# db_02.net
KiCad netlist of a schematic drawn in EAGLE
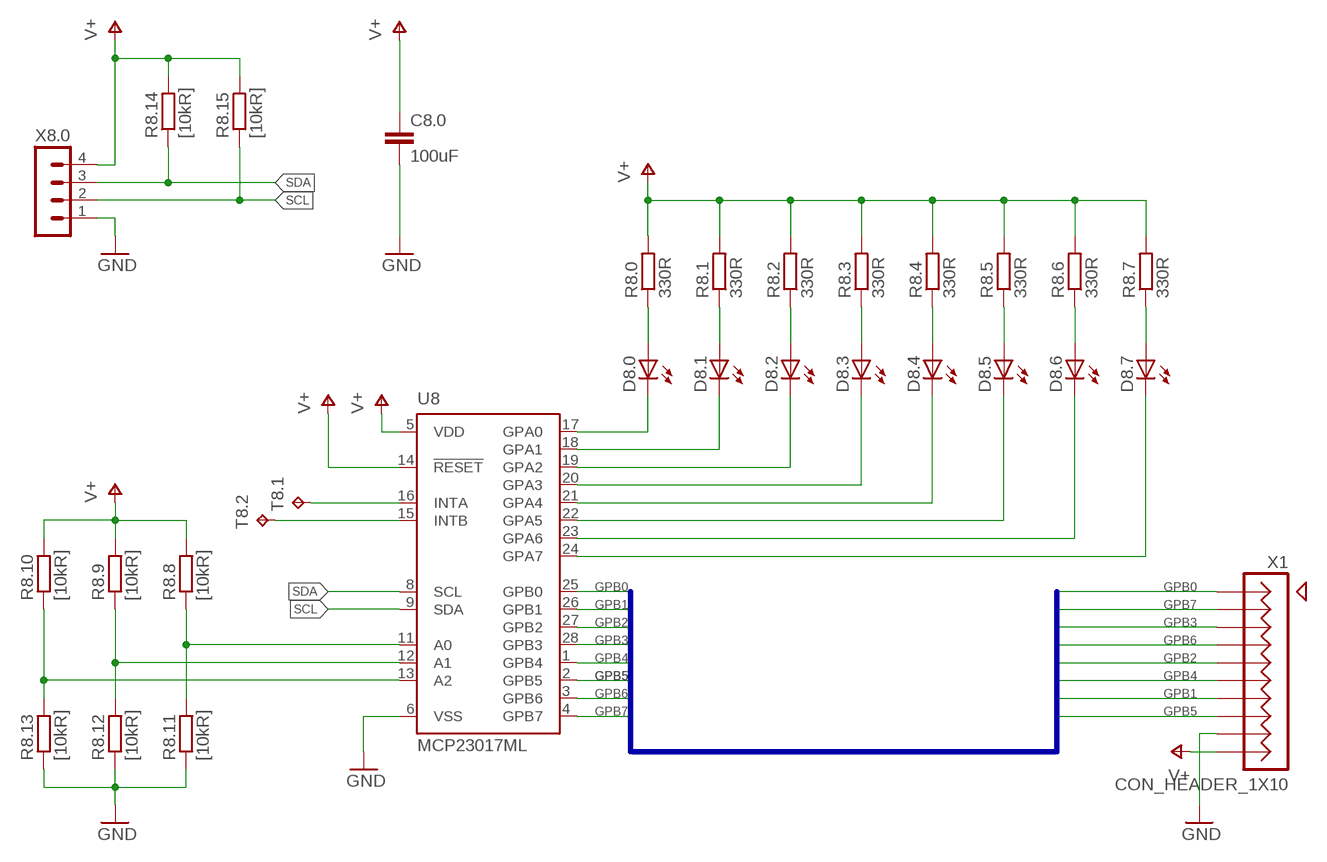
[diagram p0: schematic, sheet 1]

(export (version "E")
  (design (tool "Eeschema 10.0.6"))
  (components
    (comp (ref "C8.0")
      (value "100uF")
      (footprint "eagle-import:C0603")
      (libsource (lib "eagle-import") (part "C-EUC0603"))
    )
    (comp (ref "D8.0")
      (value "LEDCHIPLED_1206")
      (footprint "eagle-import:CHIPLED_1206")
      (libsource (lib "eagle-import") (part "LEDCHIPLED_1206"))
    )
    (comp (ref "D8.1")
      (value "LEDCHIPLED_1206")
      (footprint "eagle-import:CHIPLED_1206")
      (libsource (lib "eagle-import") (part "LEDCHIPLED_1206"))
    )
    (comp (ref "D8.2")
      (value "LEDCHIPLED_1206")
      (footprint "eagle-import:CHIPLED_1206")
      (libsource (lib "eagle-import") (part "LEDCHIPLED_1206"))
    )
    (comp (ref "D8.3")
      (value "LEDCHIPLED_1206")
      (footprint "eagle-import:CHIPLED_1206")
      (libsource (lib "eagle-import") (part "LEDCHIPLED_1206"))
    )
    (comp (ref "D8.4")
      (value "LEDCHIPLED_1206")
      (footprint "eagle-import:CHIPLED_1206")
      (libsource (lib "eagle-import") (part "LEDCHIPLED_1206"))
    )
    (comp (ref "D8.5")
      (value "LEDCHIPLED_1206")
      (footprint "eagle-import:CHIPLED_1206")
      (libsource (lib "eagle-import") (part "LEDCHIPLED_1206"))
    )
    (comp (ref "D8.6")
      (value "LEDCHIPLED_1206")
      (footprint "eagle-import:CHIPLED_1206")
      (libsource (lib "eagle-import") (part "LEDCHIPLED_1206"))
    )
    (comp (ref "D8.7")
      (value "LEDCHIPLED_1206")
      (footprint "eagle-import:CHIPLED_1206")
      (libsource (lib "eagle-import") (part "LEDCHIPLED_1206"))
    )
    (comp (ref "R8.0")
      (value "330R")
      (footprint "eagle-import:R0603")
      (libsource (lib "eagle-import") (part "R-EU_R0603"))
    )
    (comp (ref "R8.1")
      (value "330R")
      (footprint "eagle-import:R0603")
      (libsource (lib "eagle-import") (part "R-EU_R0603"))
    )
    (comp (ref "R8.2")
      (value "330R")
      (footprint "eagle-import:R0603")
      (libsource (lib "eagle-import") (part "R-EU_R0603"))
    )
    (comp (ref "R8.3")
      (value "330R")
      (footprint "eagle-import:R0603")
      (libsource (lib "eagle-import") (part "R-EU_R0603"))
    )
    (comp (ref "R8.4")
      (value "330R")
      (footprint "eagle-import:R0603")
      (libsource (lib "eagle-import") (part "R-EU_R0603"))
    )
    (comp (ref "R8.5")
      (value "330R")
      (footprint "eagle-import:R0603")
      (libsource (lib "eagle-import") (part "R-EU_R0603"))
    )
    (comp (ref "R8.6")
      (value "330R")
      (footprint "eagle-import:R0603")
      (libsource (lib "eagle-import") (part "R-EU_R0603"))
    )
    (comp (ref "R8.7")
      (value "330R")
      (footprint "eagle-import:R0603")
      (libsource (lib "eagle-import") (part "R-EU_R0603"))
    )
    (comp (ref "R8.8")
      (value "[10kR]")
      (footprint "eagle-import:R0402")
      (libsource (lib "eagle-import") (part "R-EU_R0402"))
    )
    (comp (ref "R8.9")
      (value "[10kR]")
      (footprint "eagle-import:R0402")
      (libsource (lib "eagle-import") (part "R-EU_R0402"))
    )
    (comp (ref "R8.10")
      (value "[10kR]")
      (footprint "eagle-import:R0402")
      (libsource (lib "eagle-import") (part "R-EU_R0402"))
    )
    (comp (ref "R8.11")
      (value "[10kR]")
      (footprint "eagle-import:R0402")
      (libsource (lib "eagle-import") (part "R-EU_R0402"))
    )
    (comp (ref "R8.12")
      (value "[10kR]")
      (footprint "eagle-import:R0402")
      (libsource (lib "eagle-import") (part "R-EU_R0402"))
    )
    (comp (ref "R8.13")
      (value "[10kR]")
      (footprint "eagle-import:R0402")
      (libsource (lib "eagle-import") (part "R-EU_R0402"))
    )
    (comp (ref "R8.14")
      (value "[10kR]")
      (footprint "eagle-import:R0402")
      (libsource (lib "eagle-import") (part "R-EU_R0402"))
    )
    (comp (ref "R8.15")
      (value "[10kR]")
      (footprint "eagle-import:R0402")
      (libsource (lib "eagle-import") (part "R-EU_R0402"))
    )
    (comp (ref "T8.1")
      (value "TPTP09SQ")
      (footprint "eagle-import:TP09SQ")
      (libsource (lib "eagle-import") (part "TPTP09SQ"))
    )
    (comp (ref "T8.2")
      (value "TPTP09SQ")
      (footprint "eagle-import:TP09SQ")
      (libsource (lib "eagle-import") (part "TPTP09SQ"))
    )
    (comp (ref "U8")
      (value "MCP23017ML")
      (footprint "eagle-import:QFN28-ML_6X6MM")
      (fields (field (name "MF") "MICROCHIP") (field (name "MPN") "MCP23017-E/ML"))
      (libsource (lib "eagle-import") (part "MCP23017ML"))
    )
    (comp (ref "X1")
      (value "CON_HEADER_1X10")
      (footprint "eagle-import:M1X10_SMD")
      (libsource (lib "eagle-import") (part "CON_HEADER_1X10"))
    )
    (comp (ref "X8.0")
      (value "MA04-1")
      (footprint "eagle-import:MA04-1")
      (libsource (lib "eagle-import") (part "MA04-1"))
    )
  )
  (nets
    (net (code "1") (name "/GPB0") (class "Default")
      (node (ref "U8") (pin "25") (pinfunction "GPB0_25") (pintype "bidirectional"))
      (node (ref "X1") (pin "P$1") (pinfunction "P$1_P$1") (pintype "bidirectional"))
    )
    (net (code "2") (name "/GPB1") (class "Default")
      (node (ref "U8") (pin "26") (pinfunction "GPB1_26") (pintype "bidirectional"))
      (node (ref "X1") (pin "P$7") (pinfunction "P$7_P$7") (pintype "bidirectional"))
    )
    (net (code "3") (name "/GPB2") (class "Default")
      (node (ref "U8") (pin "27") (pinfunction "GPB2_27") (pintype "bidirectional"))
      (node (ref "X1") (pin "P$5") (pinfunction "P$5_P$5") (pintype "bidirectional"))
    )
    (net (code "4") (name "/GPB3") (class "Default")
      (node (ref "U8") (pin "28") (pinfunction "GPB3_28") (pintype "bidirectional"))
      (node (ref "X1") (pin "P$3") (pinfunction "P$3_P$3") (pintype "bidirectional"))
    )
    (net (code "5") (name "/GPB4") (class "Default")
      (node (ref "U8") (pin "1") (pinfunction "GPB4_1") (pintype "bidirectional"))
      (node (ref "X1") (pin "P$6") (pinfunction "P$6_P$6") (pintype "bidirectional"))
    )
    (net (code "6") (name "/GPB5") (class "Default")
      (node (ref "U8") (pin "2") (pinfunction "GPB5_2") (pintype "bidirectional"))
      (node (ref "X1") (pin "P$8") (pinfunction "P$8_P$8") (pintype "bidirectional"))
    )
    (net (code "7") (name "/GPB6") (class "Default")
      (node (ref "U8") (pin "3") (pinfunction "GPB6_3") (pintype "bidirectional"))
      (node (ref "X1") (pin "P$4") (pinfunction "P$4_P$4") (pintype "bidirectional"))
    )
    (net (code "8") (name "/GPB7") (class "Default")
      (node (ref "U8") (pin "4") (pinfunction "GPB7_4") (pintype "bidirectional"))
      (node (ref "X1") (pin "P$2") (pinfunction "P$2_P$2") (pintype "bidirectional"))
    )
    (net (code "9") (name "GND") (class "Default")
      (node (ref "C8.0") (pin "2") (pinfunction "2_2") (pintype "passive"))
      (node (ref "R8.11") (pin "1") (pinfunction "1_1") (pintype "passive"))
      (node (ref "R8.12") (pin "1") (pinfunction "1_1") (pintype "passive"))
      (node (ref "R8.13") (pin "1") (pinfunction "1_1") (pintype "passive"))
      (node (ref "U8") (pin "6") (pinfunction "VSS_6") (pintype "power_in"))
      (node (ref "X1") (pin "P$9") (pinfunction "P$9_P$9") (pintype "bidirectional"))
      (node (ref "X8.0") (pin "1") (pinfunction "1_1") (pintype "passive"))
    )
    (net (code "10") (name "Net-(D8.0-PadA)") (class "Default")
      (node (ref "D8.0") (pin "A") (pinfunction "A_A") (pintype "passive"))
      (node (ref "R8.0") (pin "1") (pinfunction "1_1") (pintype "passive"))
    )
    (net (code "11") (name "Net-(D8.1-PadA)") (class "Default")
      (node (ref "D8.1") (pin "A") (pinfunction "A_A") (pintype "passive"))
      (node (ref "R8.1") (pin "1") (pinfunction "1_1") (pintype "passive"))
    )
    (net (code "12") (name "Net-(D8.2-PadA)") (class "Default")
      (node (ref "D8.2") (pin "A") (pinfunction "A_A") (pintype "passive"))
      (node (ref "R8.2") (pin "1") (pinfunction "1_1") (pintype "passive"))
    )
    (net (code "13") (name "Net-(D8.3-PadA)") (class "Default")
      (node (ref "D8.3") (pin "A") (pinfunction "A_A") (pintype "passive"))
      (node (ref "R8.3") (pin "1") (pinfunction "1_1") (pintype "passive"))
    )
    (net (code "14") (name "Net-(D8.4-PadA)") (class "Default")
      (node (ref "D8.4") (pin "A") (pinfunction "A_A") (pintype "passive"))
      (node (ref "R8.4") (pin "1") (pinfunction "1_1") (pintype "passive"))
    )
    (net (code "15") (name "Net-(D8.5-PadA)") (class "Default")
      (node (ref "D8.5") (pin "A") (pinfunction "A_A") (pintype "passive"))
      (node (ref "R8.5") (pin "1") (pinfunction "1_1") (pintype "passive"))
    )
    (net (code "16") (name "Net-(D8.6-PadA)") (class "Default")
      (node (ref "D8.6") (pin "A") (pinfunction "A_A") (pintype "passive"))
      (node (ref "R8.6") (pin "1") (pinfunction "1_1") (pintype "passive"))
    )
    (net (code "17") (name "Net-(D8.7-PadA)") (class "Default")
      (node (ref "D8.7") (pin "A") (pinfunction "A_A") (pintype "passive"))
      (node (ref "R8.7") (pin "1") (pinfunction "1_1") (pintype "passive"))
    )
    (net (code "18") (name "Net-(U8-A0)") (class "Default")
      (node (ref "R8.11") (pin "2") (pinfunction "2_2") (pintype "passive"))
      (node (ref "R8.8") (pin "1") (pinfunction "1_1") (pintype "passive"))
      (node (ref "U8") (pin "11") (pinfunction "A0_11") (pintype "input"))
    )
    (net (code "19") (name "Net-(U8-A1)") (class "Default")
      (node (ref "R8.12") (pin "2") (pinfunction "2_2") (pintype "passive"))
      (node (ref "R8.9") (pin "1") (pinfunction "1_1") (pintype "passive"))
      (node (ref "U8") (pin "12") (pinfunction "A1_12") (pintype "input"))
    )
    (net (code "20") (name "Net-(U8-A2)") (class "Default")
      (node (ref "R8.10") (pin "1") (pinfunction "1_1") (pintype "passive"))
      (node (ref "R8.13") (pin "2") (pinfunction "2_2") (pintype "passive"))
      (node (ref "U8") (pin "13") (pinfunction "A2_13") (pintype "input"))
    )
    (net (code "21") (name "Net-(U8-GPA0)") (class "Default")
      (node (ref "D8.0") (pin "C") (pinfunction "C_C") (pintype "passive"))
      (node (ref "U8") (pin "17") (pinfunction "GPA0_17") (pintype "bidirectional"))
    )
    (net (code "22") (name "Net-(U8-GPA1)") (class "Default")
      (node (ref "D8.1") (pin "C") (pinfunction "C_C") (pintype "passive"))
      (node (ref "U8") (pin "18") (pinfunction "GPA1_18") (pintype "bidirectional"))
    )
    (net (code "23") (name "Net-(U8-GPA2)") (class "Default")
      (node (ref "D8.2") (pin "C") (pinfunction "C_C") (pintype "passive"))
      (node (ref "U8") (pin "19") (pinfunction "GPA2_19") (pintype "bidirectional"))
    )
    (net (code "24") (name "Net-(U8-GPA3)") (class "Default")
      (node (ref "D8.3") (pin "C") (pinfunction "C_C") (pintype "passive"))
      (node (ref "U8") (pin "20") (pinfunction "GPA3_20") (pintype "bidirectional"))
    )
    (net (code "25") (name "Net-(U8-GPA4)") (class "Default")
      (node (ref "D8.4") (pin "C") (pinfunction "C_C") (pintype "passive"))
      (node (ref "U8") (pin "21") (pinfunction "GPA4_21") (pintype "bidirectional"))
    )
    (net (code "26") (name "Net-(U8-GPA5)") (class "Default")
      (node (ref "D8.5") (pin "C") (pinfunction "C_C") (pintype "passive"))
      (node (ref "U8") (pin "22") (pinfunction "GPA5_22") (pintype "bidirectional"))
    )
    (net (code "27") (name "Net-(U8-GPA6)") (class "Default")
      (node (ref "D8.6") (pin "C") (pinfunction "C_C") (pintype "passive"))
      (node (ref "U8") (pin "23") (pinfunction "GPA6_23") (pintype "bidirectional"))
    )
    (net (code "28") (name "Net-(U8-GPA7)") (class "Default")
      (node (ref "D8.7") (pin "C") (pinfunction "C_C") (pintype "passive"))
      (node (ref "U8") (pin "24") (pinfunction "GPA7_24") (pintype "bidirectional"))
    )
    (net (code "29") (name "Net-(U8-INTA)") (class "Default")
      (node (ref "T8.1") (pin "TP") (pinfunction "TP_TP") (pintype "input"))
      (node (ref "U8") (pin "16") (pinfunction "INTA_16") (pintype "output"))
    )
    (net (code "30") (name "Net-(U8-INTB)") (class "Default")
      (node (ref "T8.2") (pin "TP") (pinfunction "TP_TP") (pintype "input"))
      (node (ref "U8") (pin "15") (pinfunction "INTB_15") (pintype "output"))
    )
    (net (code "31") (name "SCL") (class "Default")
      (node (ref "R8.15") (pin "1") (pinfunction "1_1") (pintype "passive"))
      (node (ref "U8") (pin "9") (pinfunction "SDA_9") (pintype "bidirectional"))
      (node (ref "X8.0") (pin "2") (pinfunction "2_2") (pintype "passive"))
    )
    (net (code "32") (name "SDA") (class "Default")
      (node (ref "R8.14") (pin "1") (pinfunction "1_1") (pintype "passive"))
      (node (ref "U8") (pin "8") (pinfunction "SCL_8") (pintype "input"))
      (node (ref "X8.0") (pin "3") (pinfunction "3_3") (pintype "passive"))
    )
    (net (code "33") (name "V+") (class "Default")
      (node (ref "C8.0") (pin "1") (pinfunction "1_1") (pintype "passive"))
      (node (ref "R8.0") (pin "2") (pinfunction "2_2") (pintype "passive"))
      (node (ref "R8.1") (pin "2") (pinfunction "2_2") (pintype "passive"))
      (node (ref "R8.10") (pin "2") (pinfunction "2_2") (pintype "passive"))
      (node (ref "R8.14") (pin "2") (pinfunction "2_2") (pintype "passive"))
      (node (ref "R8.15") (pin "2") (pinfunction "2_2") (pintype "passive"))
      (node (ref "R8.2") (pin "2") (pinfunction "2_2") (pintype "passive"))
      (node (ref "R8.3") (pin "2") (pinfunction "2_2") (pintype "passive"))
      (node (ref "R8.4") (pin "2") (pinfunction "2_2") (pintype "passive"))
      (node (ref "R8.5") (pin "2") (pinfunction "2_2") (pintype "passive"))
      (node (ref "R8.6") (pin "2") (pinfunction "2_2") (pintype "passive"))
      (node (ref "R8.7") (pin "2") (pinfunction "2_2") (pintype "passive"))
      (node (ref "R8.8") (pin "2") (pinfunction "2_2") (pintype "passive"))
      (node (ref "R8.9") (pin "2") (pinfunction "2_2") (pintype "passive"))
      (node (ref "U8") (pin "14") (pinfunction "~{RESET}_14") (pintype "input"))
      (node (ref "U8") (pin "5") (pinfunction "VDD_5") (pintype "power_in"))
      (node (ref "X1") (pin "P$10") (pinfunction "P$10_P$10") (pintype "bidirectional"))
      (node (ref "X8.0") (pin "4") (pinfunction "4_4") (pintype "passive"))
    )
  )
)
